# ESenseFE-DigitalControl.net
KiCad netlist of a schematic drawn in Altium Designer
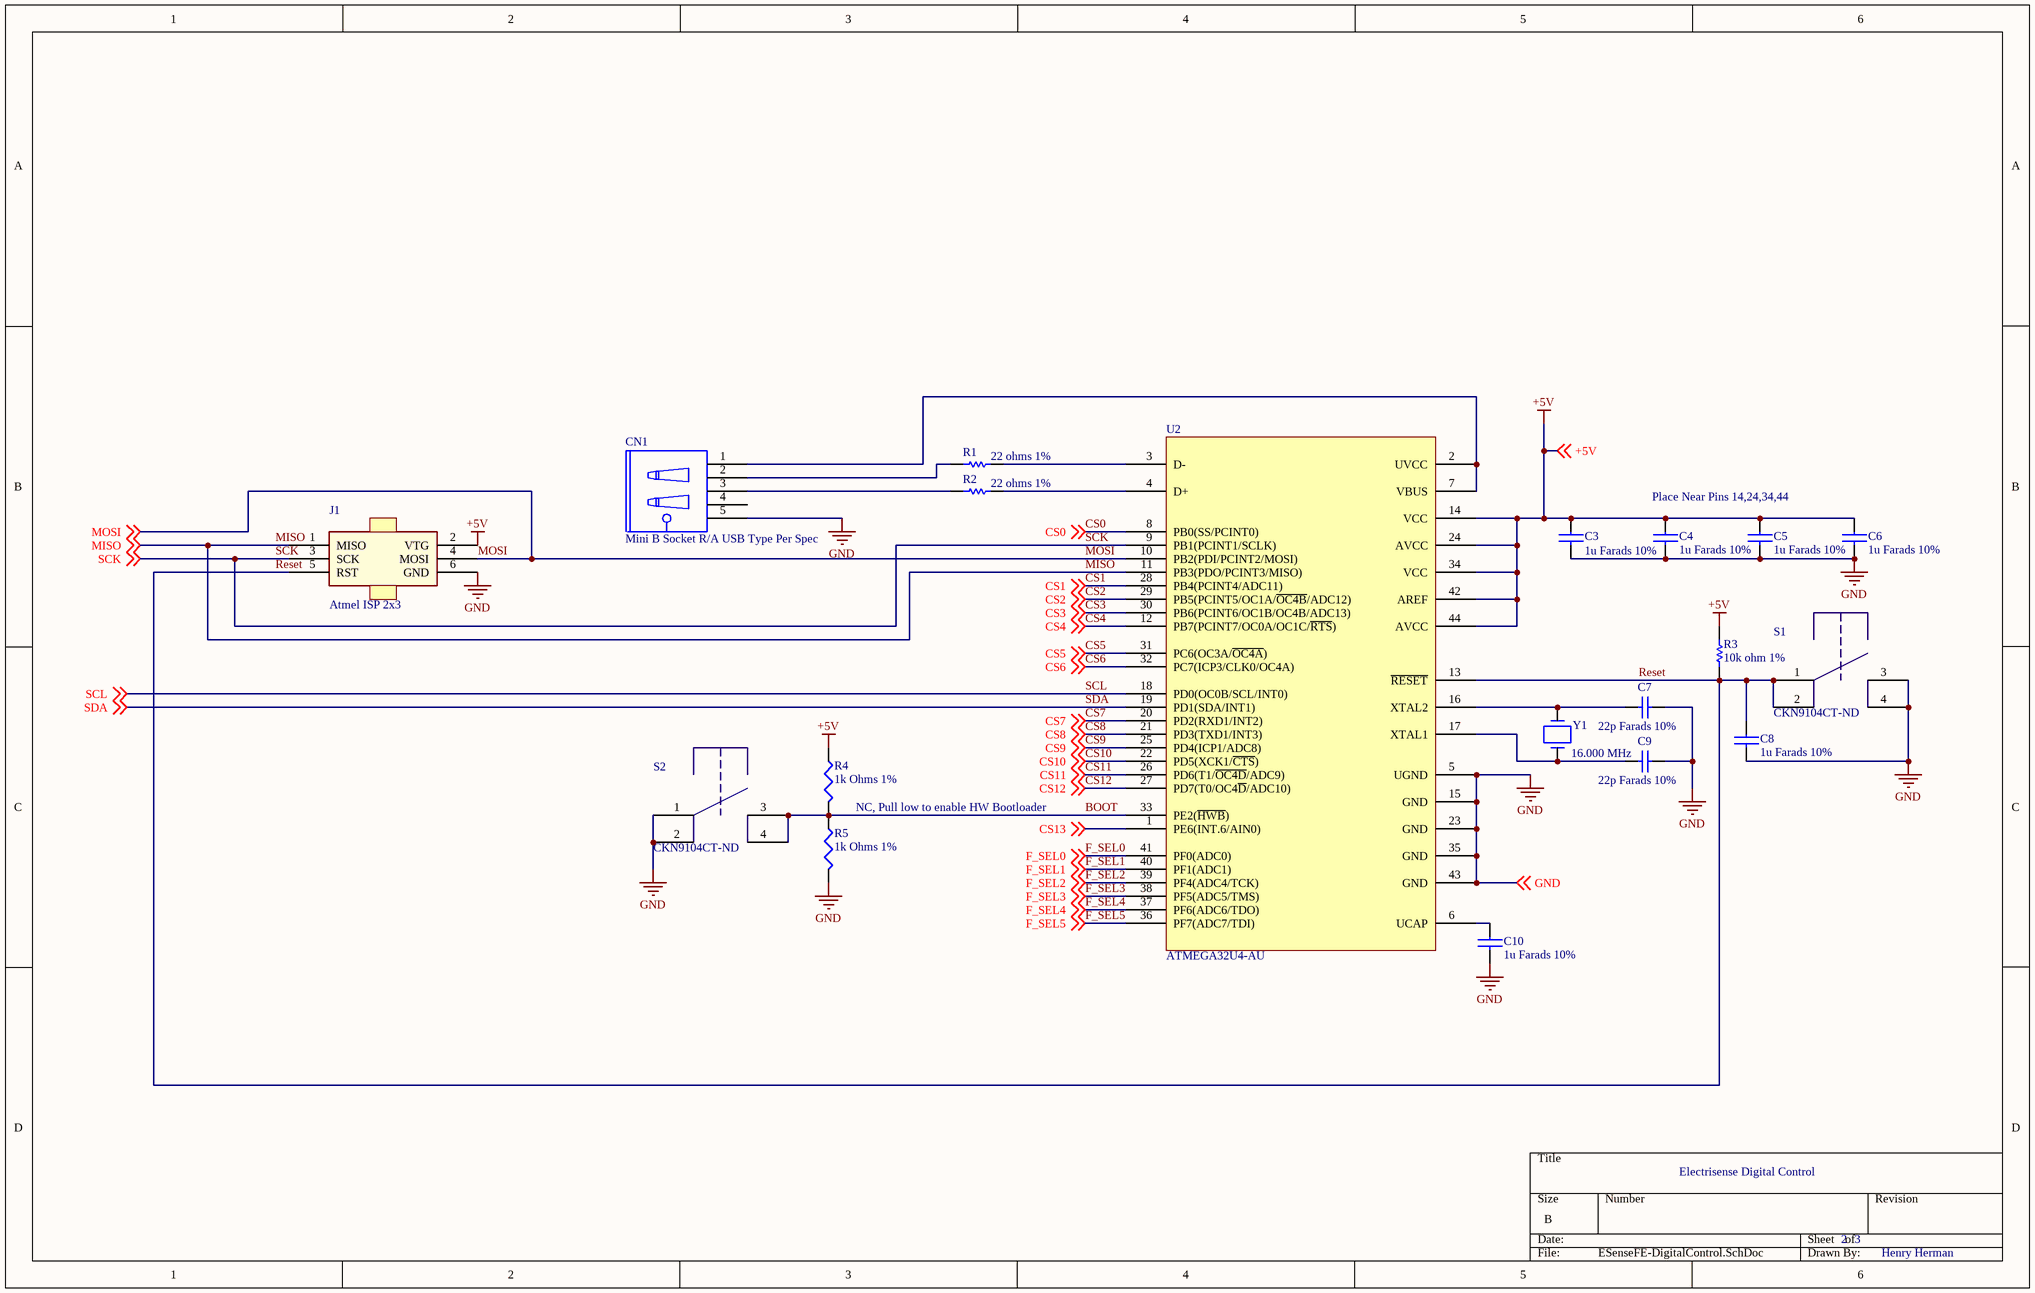
[diagram p0: ESenseFE-DigitalControl.SchDoc]

(export (version "E")
  (design (tool "Eeschema 10.0.6"))
  (components
    (comp (ref "C3")
      (value "1u Farads 10%")
      (footprint "SM/C_0603")
      (description "CAP CER 1.0UF 10V 10% X5R 0603")
      (fields (field (name "MFRPARTNUM") "GRM188R61A105KA61D"))
      (libsource (lib "FriedParts") (part "CAP NP"))
    )
    (comp (ref "C4")
      (value "1u Farads 10%")
      (footprint "SM/C_0603")
      (description "CAP CER 1.0UF 10V 10% X5R 0603")
      (fields (field (name "MFRPARTNUM") "GRM188R61A105KA61D"))
      (libsource (lib "FriedParts") (part "CAP NP"))
    )
    (comp (ref "C5")
      (value "1u Farads 10%")
      (footprint "SM/C_0603")
      (description "CAP CER 1.0UF 10V 10% X5R 0603")
      (fields (field (name "MFRPARTNUM") "GRM188R61A105KA61D"))
      (libsource (lib "FriedParts") (part "CAP NP"))
    )
    (comp (ref "C6")
      (value "1u Farads 10%")
      (footprint "SM/C_0603")
      (description "CAP CER 1.0UF 10V 10% X5R 0603")
      (fields (field (name "MFRPARTNUM") "GRM188R61A105KA61D"))
      (libsource (lib "FriedParts") (part "CAP NP"))
    )
    (comp (ref "C7")
      (value "22p Farads 10%")
      (footprint "SM/C_0603")
      (description "ceramic multilayer capacitor; capacitor type:general")
      (fields (field (name "MFRPARTNUM") "06031A220KAT2A"))
      (libsource (lib "FriedParts") (part "CAP"))
    )
    (comp (ref "C8")
      (value "1u Farads 10%")
      (footprint "SM/C_0603")
      (description "CAP CER 1.0UF 10V 10% X5R 0603")
      (fields (field (name "MFRPARTNUM") "GRM188R61A105KA61D"))
      (libsource (lib "FriedParts") (part "CAP NP"))
    )
    (comp (ref "C9")
      (value "22p Farads 10%")
      (footprint "SM/C_0603")
      (description "ceramic multilayer capacitor; capacitor type:general")
      (fields (field (name "MFRPARTNUM") "06031A220KAT2A"))
      (libsource (lib "FriedParts") (part "CAP"))
    )
    (comp (ref "C10")
      (value "1u Farads 10%")
      (footprint "SM/C_0603")
      (description "CAP CER 1.0UF 10V 10% X5R 0603")
      (fields (field (name "MFRPARTNUM") "GRM188R61A105KA61D"))
      (libsource (lib "FriedParts") (part "CAP NP"))
    )
    (comp (ref "CN1")
      (value "Mini B Socket R/A USB Type Per Spec")
      (footprint "MOLEX/54819-0579")
      (description "CONN RECEPT USB MINI-B R/A 5POS SMD")
      (fields (field (name "MFRPARTNUM") "54819-0572"))
      (libsource (lib "FriedParts") (part "USB_MINI_B/5"))
    )
    (comp (ref "J1")
      (value "Atmel ISP 2x3")
      (footprint "FCI/75867/6")
      (description "CONN HEADER 6POS DUAL R/A PCB")
      (fields (field (name "MFRPARTNUM") "75867-131LF"))
      (libsource (lib "FriedParts") (part "ATMEL/ISP6"))
    )
    (comp (ref "R1")
      (value "22 ohms 1%")
      (footprint "SM/C_0603")
      (description "rating:75v; temperature coefficient")
      (fields (field (name "MFRPARTNUM") "ERJ3EKF22R0V") (field (name "PUBLISHER") "Altium Limited"))
      (libsource (lib "FriedParts") (part "Res1"))
    )
    (comp (ref "R2")
      (value "22 ohms 1%")
      (footprint "SM/C_0603")
      (description "rating:75v; temperature coefficient")
      (fields (field (name "MFRPARTNUM") "ERJ3EKF22R0V") (field (name "PUBLISHER") "Altium Limited"))
      (libsource (lib "FriedParts") (part "Res1"))
    )
    (comp (ref "R3")
      (value "10k ohm 1%")
      (footprint "SM/C_0603")
      (description "resistor, 0603, 0.1w, 1%, 10k; resistance:10kohm; resistance")
      (fields (field (name "MFRPARTNUM") "ERJ-3EKF1002V") (field (name "PUBLISHER") "Altium Limited"))
      (libsource (lib "FriedParts") (part "Res1"))
    )
    (comp (ref "R4")
      (value "1k Ohms 1%")
      (footprint "SM/C_0603")
      (description "RES 1.00K OHM 1/10W 1% 0603 SMD")
      (fields (field (name "MFRPARTNUM") "ERJ-3EKF1001V"))
      (libsource (lib "FriedParts") (part "R"))
    )
    (comp (ref "R5")
      (value "1k Ohms 1%")
      (footprint "SM/C_0603")
      (description "RES 1.00K OHM 1/10W 1% 0603 SMD")
      (fields (field (name "MFRPARTNUM") "ERJ-3EKF1001V"))
      (libsource (lib "FriedParts") (part "R"))
    )
    (comp (ref "S1")
      (value "CKN9104CT-ND")
      (footprint "MOM-SW")
      (description "SW - SPST-NO - SM")
      (libsource (lib "FriedParts") (part "MOM-BUT"))
    )
    (comp (ref "S2")
      (value "CKN9104CT-ND")
      (footprint "MOM-SW")
      (description "SW - SPST-NO - SM")
      (libsource (lib "FriedParts") (part "MOM-BUT"))
    )
    (comp (ref "U2")
      (value "ATMEGA32U4-AU")
      (footprint "TQFP80P1200X1200X120-44L")
      (description "mcu, 8bit, avr, 32k flash, usb, 44tqfp; eeprom memory")
      (libsource (lib "FriedParts") (part "ATMega32U4"))
    )
    (comp (ref "Y1")
      (value "16.000 MHz")
      (footprint "ECS/CSM-7/2")
      (description "CRYSTAL 16.00MHZ 20PF SMD")
      (fields (field (name "MFRPARTNUM") "ECS-160-20-5P-TR"))
      (libsource (lib "FriedParts") (part "CRYSTAL"))
    )
  )
  (nets
    (net (code "1") (name "+5V") (class "Default")
      (node (ref "C3") (pin "1") (pinfunction "1_1") (pintype "passive"))
      (node (ref "C4") (pin "1") (pinfunction "1_1") (pintype "passive"))
      (node (ref "C5") (pin "1") (pinfunction "1_1") (pintype "passive"))
      (node (ref "C6") (pin "1") (pinfunction "1_1") (pintype "passive"))
      (node (ref "J1") (pin "2") (pinfunction "VTG_2") (pintype "passive"))
      (node (ref "R3") (pin "2") (pinfunction "2_2") (pintype "passive"))
      (node (ref "R4") (pin "1") (pinfunction "1_1") (pintype "passive"))
      (node (ref "U2") (pin "14") (pinfunction "VCC_14") (pintype "passive"))
      (node (ref "U2") (pin "24") (pinfunction "AVCC_24") (pintype "passive"))
      (node (ref "U2") (pin "34") (pinfunction "VCC_34") (pintype "passive"))
      (node (ref "U2") (pin "42") (pinfunction "AREF_42") (pintype "passive"))
      (node (ref "U2") (pin "44") (pinfunction "AVCC_44") (pintype "passive"))
    )
    (net (code "2") (name "/BOOT") (class "Default")
      (node (ref "R4") (pin "2") (pinfunction "2_2") (pintype "passive"))
      (node (ref "R5") (pin "1") (pinfunction "1_1") (pintype "passive"))
      (node (ref "S2") (pin "3") (pinfunction "3_3") (pintype "passive"))
      (node (ref "S2") (pin "4") (pinfunction "4_4") (pintype "passive"))
      (node (ref "U2") (pin "33") (pinfunction "PE2(~{HWB})_33") (pintype "passive"))
    )
    (net (code "3") (name "/Reset") (class "Default")
      (node (ref "C8") (pin "1") (pinfunction "1_1") (pintype "passive"))
      (node (ref "J1") (pin "5") (pinfunction "RST_5") (pintype "passive"))
      (node (ref "R3") (pin "1") (pinfunction "1_1") (pintype "passive"))
      (node (ref "S1") (pin "1") (pinfunction "1_1") (pintype "passive"))
      (node (ref "S1") (pin "2") (pinfunction "2_2") (pintype "passive"))
      (node (ref "U2") (pin "13") (pinfunction "~{RESET}_13") (pintype "passive"))
    )
    (net (code "4") (name "CS0") (class "Default")
      (node (ref "U2") (pin "8") (pinfunction "PB0(SS/PCINT0)_8") (pintype "passive"))
    )
    (net (code "5") (name "CS1") (class "Default")
      (node (ref "U2") (pin "28") (pinfunction "PB4(PCINT4/ADC11)_28") (pintype "passive"))
    )
    (net (code "6") (name "CS2") (class "Default")
      (node (ref "U2") (pin "29") (pinfunction "PB5(PCINT5/OC1A/~{OC4B}/ADC12)_29") (pintype "passive"))
    )
    (net (code "7") (name "CS3") (class "Default")
      (node (ref "U2") (pin "30") (pinfunction "PB6(PCINT6/OC1B/OC4B/ADC13)_30") (pintype "passive"))
    )
    (net (code "8") (name "CS4") (class "Default")
      (node (ref "U2") (pin "12") (pinfunction "PB7(PCINT7/OC0A/OC1C/~{RTS})_12") (pintype "passive"))
    )
    (net (code "9") (name "CS5") (class "Default")
      (node (ref "U2") (pin "31") (pinfunction "PC6(OC3A/~{OC4A})_31") (pintype "passive"))
    )
    (net (code "10") (name "CS6") (class "Default")
      (node (ref "U2") (pin "32") (pinfunction "PC7(ICP3/CLK0/OC4A)_32") (pintype "passive"))
    )
    (net (code "11") (name "CS7") (class "Default")
      (node (ref "U2") (pin "20") (pinfunction "PD2(RXD1/INT2)_20") (pintype "passive"))
    )
    (net (code "12") (name "CS8") (class "Default")
      (node (ref "U2") (pin "21") (pinfunction "PD3(TXD1/INT3)_21") (pintype "passive"))
    )
    (net (code "13") (name "CS9") (class "Default")
      (node (ref "U2") (pin "25") (pinfunction "PD4(ICP1/ADC8)_25") (pintype "passive"))
    )
    (net (code "14") (name "CS10") (class "Default")
      (node (ref "U2") (pin "22") (pinfunction "PD5(XCK1/~{CTS})_22") (pintype "passive"))
    )
    (net (code "15") (name "CS11") (class "Default")
      (node (ref "U2") (pin "26") (pinfunction "PD6(T1/~{OC4D}/ADC9)_26") (pintype "passive"))
    )
    (net (code "16") (name "CS12") (class "Default")
      (node (ref "U2") (pin "27") (pinfunction "PD7(T0/OC4~{D}/ADC10)_27") (pintype "passive"))
    )
    (net (code "17") (name "CS13") (class "Default")
      (node (ref "U2") (pin "1") (pinfunction "PE6(INT.6/AIN0)_1") (pintype "passive"))
    )
    (net (code "18") (name "F_SEL0") (class "Default")
      (node (ref "U2") (pin "41") (pinfunction "PF0(ADC0)_41") (pintype "passive"))
    )
    (net (code "19") (name "F_SEL1") (class "Default")
      (node (ref "U2") (pin "40") (pinfunction "PF1(ADC1)_40") (pintype "passive"))
    )
    (net (code "20") (name "F_SEL2") (class "Default")
      (node (ref "U2") (pin "39") (pinfunction "PF4(ADC4/TCK)_39") (pintype "passive"))
    )
    (net (code "21") (name "F_SEL3") (class "Default")
      (node (ref "U2") (pin "38") (pinfunction "PF5(ADC5/TMS)_38") (pintype "passive"))
    )
    (net (code "22") (name "F_SEL4") (class "Default")
      (node (ref "U2") (pin "37") (pinfunction "PF6(ADC6/TDO)_37") (pintype "passive"))
    )
    (net (code "23") (name "F_SEL5") (class "Default")
      (node (ref "U2") (pin "36") (pinfunction "PF7(ADC7/TDI)_36") (pintype "passive"))
    )
    (net (code "24") (name "GND") (class "Default")
      (node (ref "C10") (pin "2") (pinfunction "2_2") (pintype "passive"))
      (node (ref "C3") (pin "2") (pinfunction "2_2") (pintype "passive"))
      (node (ref "C4") (pin "2") (pinfunction "2_2") (pintype "passive"))
      (node (ref "C5") (pin "2") (pinfunction "2_2") (pintype "passive"))
      (node (ref "C6") (pin "2") (pinfunction "2_2") (pintype "passive"))
      (node (ref "C7") (pin "2") (pinfunction "2_2") (pintype "passive"))
      (node (ref "C8") (pin "2") (pinfunction "2_2") (pintype "passive"))
      (node (ref "C9") (pin "2") (pinfunction "2_2") (pintype "passive"))
      (node (ref "CN1") (pin "5") (pinfunction "5_5") (pintype "passive"))
      (node (ref "J1") (pin "6") (pinfunction "GND_6") (pintype "passive"))
      (node (ref "R5") (pin "2") (pinfunction "2_2") (pintype "passive"))
      (node (ref "S1") (pin "3") (pinfunction "3_3") (pintype "passive"))
      (node (ref "S1") (pin "4") (pinfunction "4_4") (pintype "passive"))
      (node (ref "S2") (pin "1") (pinfunction "1_1") (pintype "passive"))
      (node (ref "S2") (pin "2") (pinfunction "2_2") (pintype "passive"))
      (node (ref "U2") (pin "15") (pinfunction "GND_15") (pintype "passive"))
      (node (ref "U2") (pin "23") (pinfunction "GND_23") (pintype "passive"))
      (node (ref "U2") (pin "35") (pinfunction "GND_35") (pintype "passive"))
      (node (ref "U2") (pin "43") (pinfunction "GND_43") (pintype "passive"))
      (node (ref "U2") (pin "5") (pinfunction "UGND_5") (pintype "passive"))
    )
    (net (code "25") (name "MISO") (class "Default")
      (node (ref "J1") (pin "1") (pinfunction "MISO_1") (pintype "passive"))
      (node (ref "U2") (pin "11") (pinfunction "PB3(PDO/PCINT3/MISO)_11") (pintype "passive"))
    )
    (net (code "26") (name "MOSI") (class "Default")
      (node (ref "J1") (pin "4") (pinfunction "MOSI_4") (pintype "passive"))
      (node (ref "U2") (pin "10") (pinfunction "PB2(PDI/PCINT2/MOSI)_10") (pintype "passive"))
    )
    (net (code "27") (name "Net-(CN1-Pad2)") (class "Default")
      (node (ref "CN1") (pin "2") (pinfunction "2_2") (pintype "passive"))
      (node (ref "R1") (pin "1") (pinfunction "1_1") (pintype "passive"))
    )
    (net (code "28") (name "Net-(CN1-Pad3)") (class "Default")
      (node (ref "CN1") (pin "3") (pinfunction "3_3") (pintype "passive"))
      (node (ref "R2") (pin "1") (pinfunction "1_1") (pintype "passive"))
    )
    (net (code "29") (name "Net-(U2-D+)") (class "Default")
      (node (ref "R2") (pin "2") (pinfunction "2_2") (pintype "passive"))
      (node (ref "U2") (pin "4") (pinfunction "D+_4") (pintype "passive"))
    )
    (net (code "30") (name "Net-(U2-D-)") (class "Default")
      (node (ref "R1") (pin "2") (pinfunction "2_2") (pintype "passive"))
      (node (ref "U2") (pin "3") (pinfunction "D-_3") (pintype "passive"))
    )
    (net (code "31") (name "Net-(U2-UCAP)") (class "Default")
      (node (ref "C10") (pin "1") (pinfunction "1_1") (pintype "passive"))
      (node (ref "U2") (pin "6") (pinfunction "UCAP_6") (pintype "passive"))
    )
    (net (code "32") (name "Net-(U2-UVCC)") (class "Default")
      (node (ref "CN1") (pin "1") (pinfunction "1_1") (pintype "passive"))
      (node (ref "U2") (pin "2") (pinfunction "UVCC_2") (pintype "passive"))
      (node (ref "U2") (pin "7") (pinfunction "VBUS_7") (pintype "passive"))
    )
    (net (code "33") (name "Net-(U2-XTAL1)") (class "Default")
      (node (ref "C9") (pin "1") (pinfunction "1_1") (pintype "passive"))
      (node (ref "U2") (pin "17") (pinfunction "XTAL1_17") (pintype "passive"))
      (node (ref "Y1") (pin "1") (pinfunction "1_1") (pintype "passive"))
    )
    (net (code "34") (name "Net-(U2-XTAL2)") (class "Default")
      (node (ref "C7") (pin "1") (pinfunction "1_1") (pintype "passive"))
      (node (ref "U2") (pin "16") (pinfunction "XTAL2_16") (pintype "passive"))
      (node (ref "Y1") (pin "2") (pinfunction "2_2") (pintype "passive"))
    )
    (net (code "35") (name "SCK") (class "Default")
      (node (ref "J1") (pin "3") (pinfunction "SCK_3") (pintype "passive"))
      (node (ref "U2") (pin "9") (pinfunction "PB1(PCINT1/SCLK)_9") (pintype "passive"))
    )
    (net (code "36") (name "SCL") (class "Default")
      (node (ref "U2") (pin "18") (pinfunction "PD0(OC0B/SCL/INT0)_18") (pintype "passive"))
    )
    (net (code "37") (name "SDA") (class "Default")
      (node (ref "U2") (pin "19") (pinfunction "PD1(SDA/INT1)_19") (pintype "passive"))
    )
    (net (code "38") (name "unconnected-(CN1-Pad4)") (class "Default")
      (node (ref "CN1") (pin "4") (pinfunction "4_4") (pintype "passive"))
    )
  )
)
